# McPiFace-60mmFan-V4_0.net
KiCad netlist of a schematic drawn in EAGLE
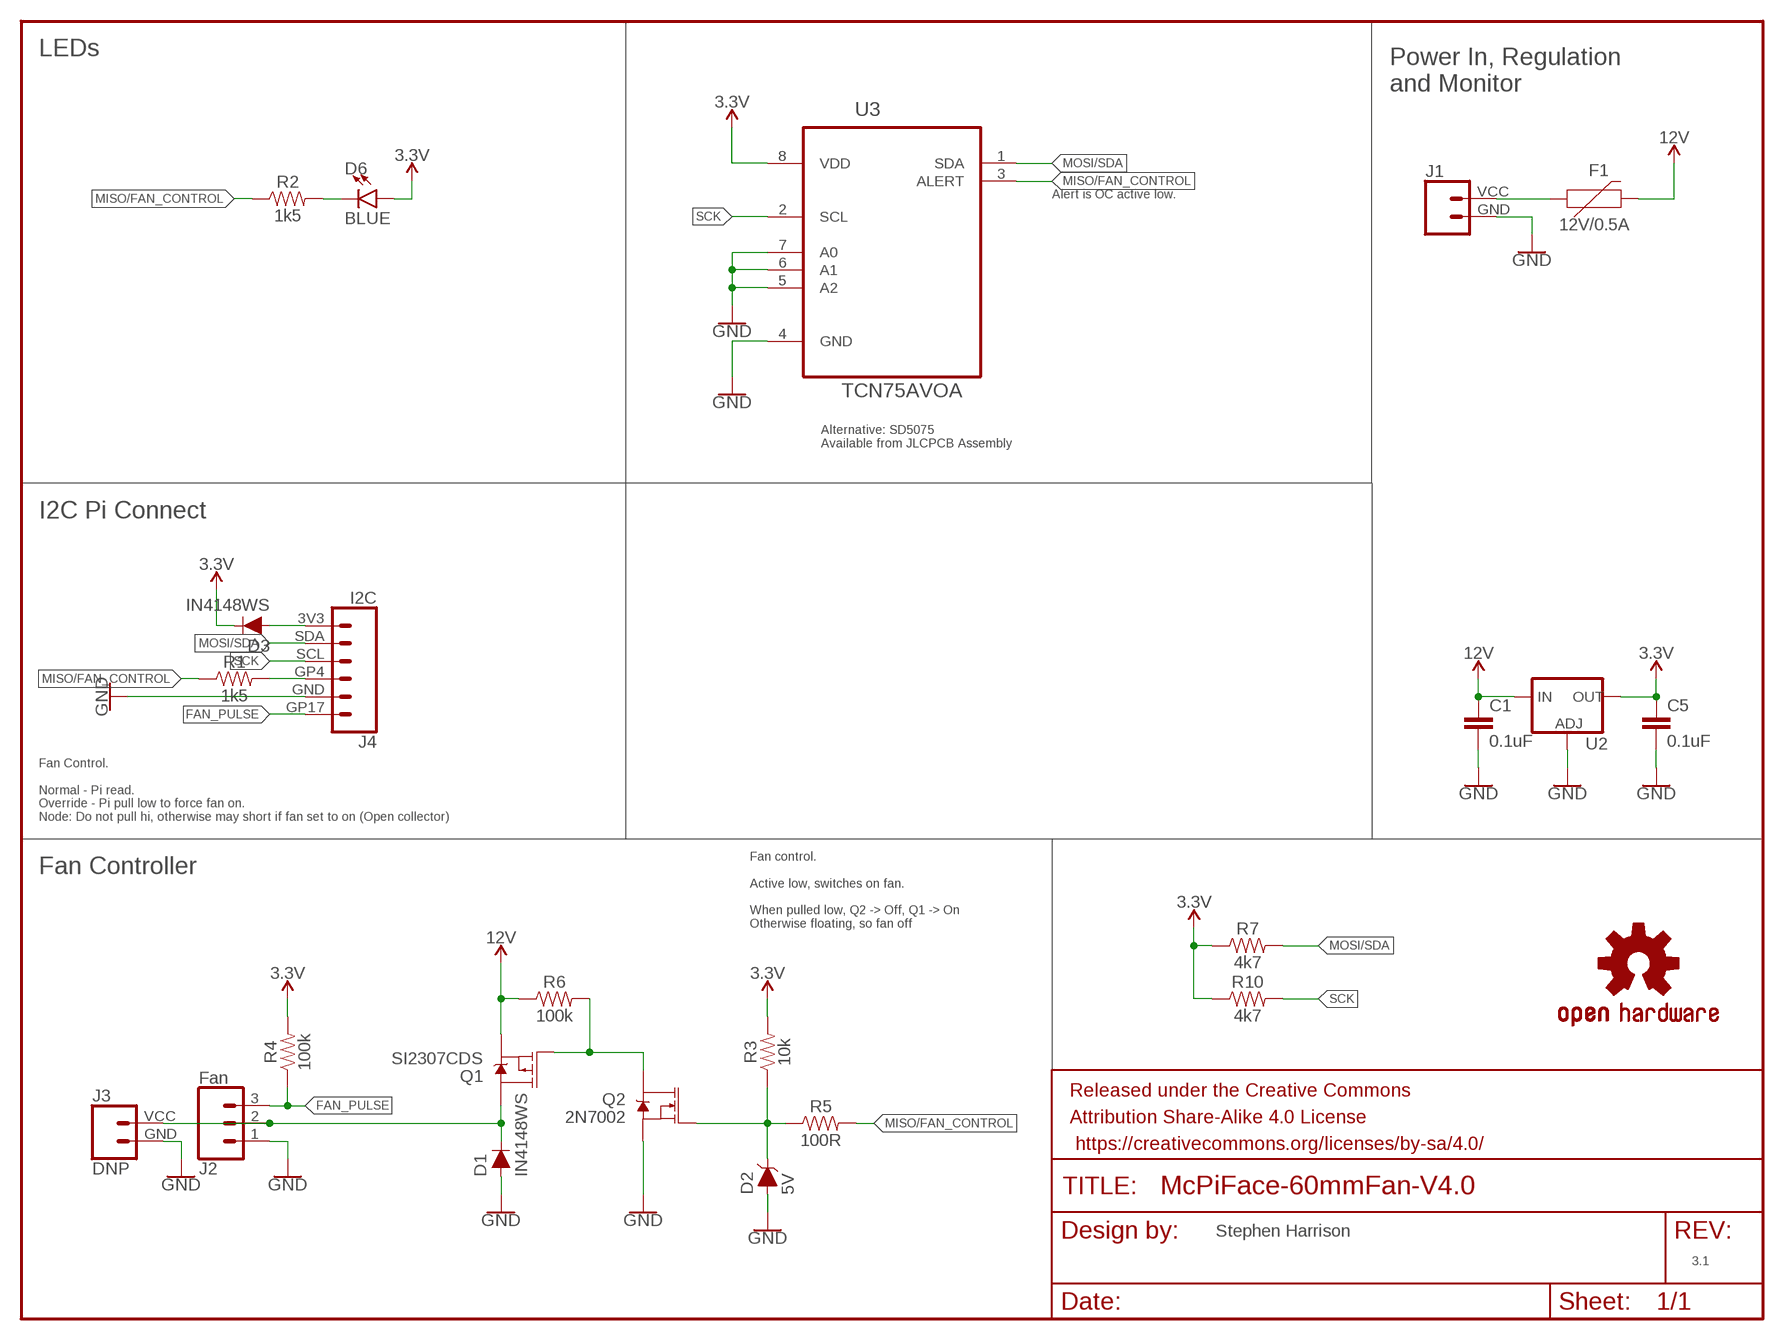
[diagram p0: schematic, sheet 1]

(export (version "E")
  (design (tool "Eeschema 10.0.6"))
  (components
    (comp (ref "C1")
      (value "0.1uF")
      (footprint "eagle-import:0805")
      (libsource (lib "eagle-import") (part "0.1UF-0805-25V"))
    )
    (comp (ref "C5")
      (value "0.1uF")
      (footprint "eagle-import:0805")
      (libsource (lib "eagle-import") (part "0.1UF-0805-25V"))
    )
    (comp (ref "D1")
      (value "IN4148WS")
      (footprint "eagle-import:SOD-323")
      (libsource (lib "eagle-import") (part "DIODE-BAS16J"))
    )
    (comp (ref "D2")
      (value "5V")
      (footprint "eagle-import:SOD-323")
      (libsource (lib "eagle-import") (part "DIODE-ZENER-BZT52C3V6S"))
    )
    (comp (ref "D3")
      (value "IN4148WS")
      (footprint "eagle-import:SOD-323")
      (libsource (lib "eagle-import") (part "DIODE-BAS16J"))
    )
    (comp (ref "D6")
      (value "BLUE")
      (footprint "eagle-import:LED-1206")
      (libsource (lib "eagle-import") (part "LED1206"))
    )
    (comp (ref "F1")
      (value "12V/0.5A")
      (footprint "eagle-import:1206")
      (libsource (lib "eagle-import") (part "PPTC_HALF-AMP"))
    )
    (comp (ref "FRAME1")
      (value "FRAME-LETTER")
      (footprint "eagle-import:CREATIVE_COMMONS")
      (libsource (lib "eagle-import") (part "FRAME-LETTER"))
    )
    (comp (ref "J1")
      (value "CONN_024UCON-15767")
      (footprint "eagle-import:JST-2-SMD-VERT")
      (libsource (lib "eagle-import") (part "CONN_024UCON-15767"))
    )
    (comp (ref "J2")
      (value "Fan")
      (footprint "eagle-import:JST-3-SMD")
      (fields (field (name "MFG") "S3B-PH-SM4-TB(LF)(SN)"))
      (libsource (lib "eagle-import") (part "CONN_03JST-SMD"))
    )
    (comp (ref "J3")
      (value "DNP")
      (footprint "eagle-import:JST-2-SMD-VERT")
      (libsource (lib "eagle-import") (part "CONN_024UCON-15767"))
    )
    (comp (ref "J4")
      (value "I2C")
      (footprint "eagle-import:JST-6-SH-1.0MM-TOP")
      (libsource (lib "eagle-import") (part "MC_PI_FACE_I2CTOP"))
    )
    (comp (ref "LOGO1")
      (value "OSHW-LOGOL")
      (footprint "eagle-import:OSHW-LOGO-L")
      (libsource (lib "eagle-import") (part "OSHW-LOGOL"))
    )
    (comp (ref "Q1")
      (value "SI2307CDS")
      (footprint "eagle-import:SOT23-3")
      (libsource (lib "eagle-import") (part "MOSFET_PCH-IRLML2244"))
    )
    (comp (ref "Q2")
      (value "2N7002")
      (footprint "eagle-import:SOT23-3")
      (libsource (lib "eagle-import") (part "MOSFET-NCH-BSS138"))
    )
    (comp (ref "R1")
      (value "1k5")
      (footprint "eagle-import:0805")
      (libsource (lib "eagle-import") (part "RESISTOR0805"))
    )
    (comp (ref "R2")
      (value "1k5")
      (footprint "eagle-import:0805")
      (libsource (lib "eagle-import") (part "RESISTOR0805"))
    )
    (comp (ref "R3")
      (value "10k")
      (footprint "eagle-import:0805")
      (libsource (lib "eagle-import") (part "RESISTOR0805"))
    )
    (comp (ref "R4")
      (value "100k")
      (footprint "eagle-import:0805")
      (libsource (lib "eagle-import") (part "RESISTOR0805"))
    )
    (comp (ref "R5")
      (value "100R")
      (footprint "eagle-import:0805")
      (libsource (lib "eagle-import") (part "RESISTOR0805"))
    )
    (comp (ref "R6")
      (value "100k")
      (footprint "eagle-import:0805")
      (libsource (lib "eagle-import") (part "RESISTOR0805"))
    )
    (comp (ref "R7")
      (value "4k7")
      (footprint "eagle-import:0805")
      (libsource (lib "eagle-import") (part "RESISTOR0805"))
    )
    (comp (ref "R10")
      (value "4k7")
      (footprint "eagle-import:0805")
      (libsource (lib "eagle-import") (part "RESISTOR0805"))
    )
    (comp (ref "U2")
      (value "V_REG_LM1117SOT223")
      (footprint "eagle-import:SOT223")
      (libsource (lib "eagle-import") (part "V_REG_LM1117SOT223"))
    )
    (comp (ref "U3")
      (value "TCN75AVOA")
      (footprint "eagle-import:SOIC127P600X175-8N")
      (fields (field (name "MPN") "TCN75AVOA "))
      (libsource (lib "eagle-import") (part "TCN75AVOA"))
    )
  )
  (nets
    (net (code "1") (name "3.3V") (class "Default")
      (node (ref "C5") (pin "1") (pinfunction "1_1") (pintype "passive"))
      (node (ref "D3") (pin "C") (pinfunction "C_C") (pintype "passive"))
      (node (ref "D6") (pin "A") (pinfunction "A_A") (pintype "passive"))
      (node (ref "R10") (pin "1") (pinfunction "1_1") (pintype "passive"))
      (node (ref "R3") (pin "2") (pinfunction "2_2") (pintype "passive"))
      (node (ref "R4") (pin "2") (pinfunction "2_2") (pintype "passive"))
      (node (ref "R7") (pin "1") (pinfunction "1_1") (pintype "passive"))
      (node (ref "U2") (pin "2") (pinfunction "OUT_2") (pintype "output"))
      (node (ref "U2") (pin "4") (pinfunction "OUT_4") (pintype "output"))
      (node (ref "U3") (pin "8") (pinfunction "VDD_8") (pintype "power_in"))
    )
    (net (code "2") (name "12V") (class "Default")
      (node (ref "C1") (pin "1") (pinfunction "1_1") (pintype "passive"))
      (node (ref "F1") (pin "2") (pinfunction "2_2") (pintype "bidirectional"))
      (node (ref "Q1") (pin "2") (pinfunction "S_2") (pintype "bidirectional"))
      (node (ref "R6") (pin "1") (pinfunction "1_1") (pintype "passive"))
      (node (ref "U2") (pin "3") (pinfunction "IN_3") (pintype "input"))
    )
    (net (code "3") (name "FAN_PULSE") (class "Default")
      (node (ref "J2") (pin "3") (pinfunction "1_3") (pintype "passive"))
      (node (ref "J4") (pin "GP17") (pinfunction "GP17_GP17") (pintype "bidirectional"))
      (node (ref "R4") (pin "1") (pinfunction "1_1") (pintype "passive"))
    )
    (net (code "4") (name "GND") (class "Default")
      (node (ref "C1") (pin "2") (pinfunction "2_2") (pintype "passive"))
      (node (ref "C5") (pin "2") (pinfunction "2_2") (pintype "passive"))
      (node (ref "D1") (pin "A") (pinfunction "A_A") (pintype "passive"))
      (node (ref "D2") (pin "A") (pinfunction "A_A") (pintype "passive"))
      (node (ref "J1") (pin "GND") (pinfunction "1_GND") (pintype "passive"))
      (node (ref "J2") (pin "1") (pinfunction "3_1") (pintype "passive"))
      (node (ref "J3") (pin "GND") (pinfunction "1_GND") (pintype "passive"))
      (node (ref "J4") (pin "GND") (pinfunction "GND_GND") (pintype "power_in"))
      (node (ref "Q2") (pin "2") (pinfunction "S_2") (pintype "bidirectional"))
      (node (ref "U2") (pin "1") (pinfunction "ADJ_1") (pintype "input"))
      (node (ref "U3") (pin "4") (pinfunction "GND_4") (pintype "power_in"))
      (node (ref "U3") (pin "5") (pinfunction "A2_5") (pintype "input"))
      (node (ref "U3") (pin "6") (pinfunction "A1_6") (pintype "input"))
      (node (ref "U3") (pin "7") (pinfunction "A0_7") (pintype "input"))
    )
    (net (code "5") (name "MISO{slash}FAN_CONTROL") (class "Default")
      (node (ref "R1") (pin "1") (pinfunction "1_1") (pintype "passive"))
      (node (ref "R2") (pin "1") (pinfunction "1_1") (pintype "passive"))
      (node (ref "R5") (pin "2") (pinfunction "2_2") (pintype "passive"))
      (node (ref "U3") (pin "3") (pinfunction "ALERT_3") (pintype "output"))
    )
    (net (code "6") (name "MOSI{slash}SDA") (class "Default")
      (node (ref "J4") (pin "SDA") (pinfunction "SDA_SDA") (pintype "bidirectional"))
      (node (ref "R7") (pin "2") (pinfunction "2_2") (pintype "passive"))
      (node (ref "U3") (pin "1") (pinfunction "SDA_1") (pintype "bidirectional"))
    )
    (net (code "7") (name "Net-(D3-PadA)") (class "Default")
      (node (ref "D3") (pin "A") (pinfunction "A_A") (pintype "passive"))
      (node (ref "J4") (pin "3V3") (pinfunction "3V3_3V3") (pintype "power_in"))
    )
    (net (code "8") (name "Net-(D6-PadC)") (class "Default")
      (node (ref "D6") (pin "C") (pinfunction "C_C") (pintype "passive"))
      (node (ref "R2") (pin "2") (pinfunction "2_2") (pintype "passive"))
    )
    (net (code "9") (name "Net-(J1-2)") (class "Default")
      (node (ref "F1") (pin "1") (pinfunction "1_1") (pintype "bidirectional"))
      (node (ref "J1") (pin "VCC") (pinfunction "2_VCC") (pintype "passive"))
    )
    (net (code "10") (name "Net-(J3-2)") (class "Default")
      (node (ref "D1") (pin "C") (pinfunction "C_C") (pintype "passive"))
      (node (ref "J2") (pin "2") (pinfunction "2_2") (pintype "passive"))
      (node (ref "J3") (pin "VCC") (pinfunction "2_VCC") (pintype "passive"))
      (node (ref "Q1") (pin "3") (pinfunction "D_3") (pintype "bidirectional"))
    )
    (net (code "11") (name "Net-(J4-PadGP4)") (class "Default")
      (node (ref "J4") (pin "GP4") (pinfunction "GP4_GP4") (pintype "bidirectional"))
      (node (ref "R1") (pin "2") (pinfunction "2_2") (pintype "passive"))
    )
    (net (code "12") (name "Net-(Q1-G)") (class "Default")
      (node (ref "Q1") (pin "1") (pinfunction "G_1") (pintype "bidirectional"))
      (node (ref "Q2") (pin "3") (pinfunction "D_3") (pintype "bidirectional"))
      (node (ref "R6") (pin "2") (pinfunction "2_2") (pintype "passive"))
    )
    (net (code "13") (name "Net-(Q2-G)") (class "Default")
      (node (ref "D2") (pin "C") (pinfunction "C_C") (pintype "passive"))
      (node (ref "Q2") (pin "1") (pinfunction "G_1") (pintype "bidirectional"))
      (node (ref "R3") (pin "1") (pinfunction "1_1") (pintype "passive"))
      (node (ref "R5") (pin "1") (pinfunction "1_1") (pintype "passive"))
    )
    (net (code "14") (name "SCK") (class "Default")
      (node (ref "J4") (pin "SCL") (pinfunction "SCL_SCL") (pintype "bidirectional"))
      (node (ref "R10") (pin "2") (pinfunction "2_2") (pintype "passive"))
      (node (ref "U3") (pin "2") (pinfunction "SCL_2") (pintype "input"))
    )
  )
)
